# GL3227_Core.net
KiCad netlist of a schematic drawn in Altium Designer
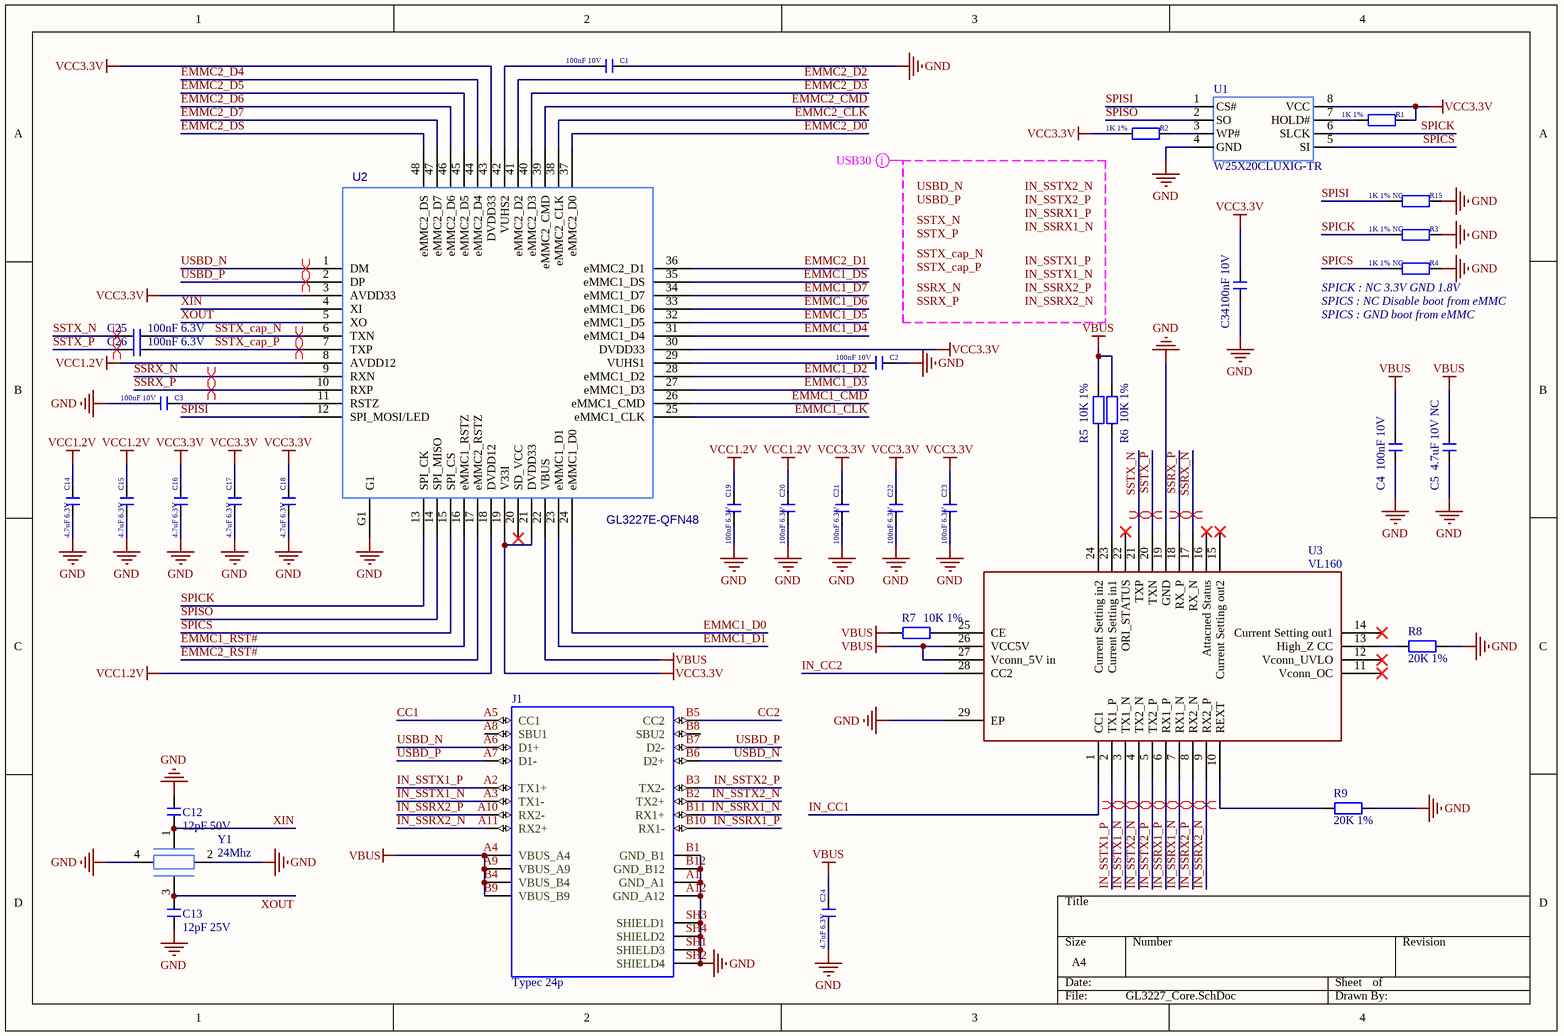
[diagram p0: GL3227_Core.SchDoc]

(export (version "E")
  (design (tool "Eeschema 10.0.6"))
  (components
    (comp (ref "C1")
      (value "100nF 10V")
      (footprint "C0402_NS")
      (description "无极性贴片电容")
      (fields (field (name "版权归属") "源创客"))
      (libsource (lib "Capacitor") (part "C"))
    )
    (comp (ref "C2")
      (value "100nF 10V")
      (footprint "C0402_NS")
      (description "无极性贴片电容")
      (fields (field (name "版权归属") "源创客"))
      (libsource (lib "Capacitor") (part "C"))
    )
    (comp (ref "C3")
      (value "100nF 10V")
      (footprint "C0402_NS")
      (description "无极性贴片电容")
      (fields (field (name "版权归属") "源创客"))
      (libsource (lib "Capacitor") (part "C"))
    )
    (comp (ref "C4")
      (value "100nF 10V")
      (footprint "C0402_NS")
      (description "无极性贴片电容")
      (fields (field (name "版权归属") "源创客"))
      (libsource (lib "Capacitor") (part "C"))
    )
    (comp (ref "C5")
      (value "4.7uF 10V NC")
      (footprint "C0402_NS")
      (description "无极性贴片电容")
      (fields (field (name "版权归属") "源创客"))
      (libsource (lib "Capacitor") (part "C"))
    )
    (comp (ref "C12")
      (value "12pF 50V")
      (footprint "C0402_NS")
      (description "无极性贴片电容")
      (fields (field (name "版权归属") "源创客"))
      (libsource (lib "Capacitor") (part "C"))
    )
    (comp (ref "C13")
      (value "12pF 25V")
      (footprint "C0402_NS")
      (description "无极性贴片电容")
      (fields (field (name "版权归属") "源创客"))
      (libsource (lib "Capacitor") (part "C"))
    )
    (comp (ref "C14")
      (value "4.7uF 6.3V")
      (footprint "C0402_NS")
      (description "无极性贴片电容")
      (fields (field (name "版权归属") "源创客"))
      (libsource (lib "Capacitor") (part "C"))
    )
    (comp (ref "C15")
      (value "4.7uF 6.3V")
      (footprint "C0402_NS")
      (description "无极性贴片电容")
      (fields (field (name "版权归属") "源创客"))
      (libsource (lib "Capacitor") (part "C"))
    )
    (comp (ref "C16")
      (value "4.7uF 6.3V")
      (footprint "C0402_NS")
      (description "无极性贴片电容")
      (fields (field (name "版权归属") "源创客"))
      (libsource (lib "Capacitor") (part "C"))
    )
    (comp (ref "C17")
      (value "4.7uF 6.3V")
      (footprint "C0402_NS")
      (description "无极性贴片电容")
      (fields (field (name "版权归属") "源创客"))
      (libsource (lib "Capacitor") (part "C"))
    )
    (comp (ref "C18")
      (value "4.7uF 6.3V")
      (footprint "C0402_NS")
      (description "无极性贴片电容")
      (fields (field (name "版权归属") "源创客"))
      (libsource (lib "Capacitor") (part "C"))
    )
    (comp (ref "C19")
      (value "100nF 6.3V")
      (footprint "C0402_NS")
      (description "无极性贴片电容")
      (fields (field (name "版权归属") "源创客"))
      (libsource (lib "Capacitor") (part "C"))
    )
    (comp (ref "C20")
      (value "100nF 6.3V")
      (footprint "C0402_NS")
      (description "无极性贴片电容")
      (fields (field (name "版权归属") "源创客"))
      (libsource (lib "Capacitor") (part "C"))
    )
    (comp (ref "C21")
      (value "100nF 6.3V")
      (footprint "C0402_NS")
      (description "无极性贴片电容")
      (fields (field (name "版权归属") "源创客"))
      (libsource (lib "Capacitor") (part "C"))
    )
    (comp (ref "C22")
      (value "100nF 6.3V")
      (footprint "C0402_NS")
      (description "无极性贴片电容")
      (fields (field (name "版权归属") "源创客"))
      (libsource (lib "Capacitor") (part "C"))
    )
    (comp (ref "C23")
      (value "100nF 6.3V")
      (footprint "C0402_NS")
      (description "无极性贴片电容")
      (fields (field (name "版权归属") "源创客"))
      (libsource (lib "Capacitor") (part "C"))
    )
    (comp (ref "C24")
      (value "4.7uF 6.3V")
      (footprint "C0402_NS")
      (description "无极性贴片电容")
      (fields (field (name "版权归属") "源创客"))
      (libsource (lib "Capacitor") (part "C"))
    )
    (comp (ref "C25")
      (value "100nF 6.3V")
      (footprint "C0402_NS")
      (description "无极性贴片电容")
      (fields (field (name "版权归属") "源创客"))
      (libsource (lib "Capacitor") (part "C"))
    )
    (comp (ref "C26")
      (value "100nF 6.3V")
      (footprint "C0402_NS")
      (description "无极性贴片电容")
      (fields (field (name "版权归属") "源创客"))
      (libsource (lib "Capacitor") (part "C"))
    )
    (comp (ref "C34")
      (value "100nF 10V")
      (footprint "C0402_NS")
      (description "无极性贴片电容")
      (fields (field (name "版权归属") "源创客"))
      (libsource (lib "Capacitor") (part "C"))
    )
    (comp (ref "J1")
      (value "Typec 24p")
      (footprint "USB-C-SMD_TYPEC-1103-BRP24")
      (fields (field (name "MF") "Molex") (field (name "MP") "1054500101"))
      (libsource (lib "Connector-USB") (part "Typec 24p"))
    )
    (comp (ref "R1")
      (value "1K 1%")
      (footprint "R0402_NS")
      (description "贴片电阻")
      (fields (field (name "版权归属") "源创客"))
      (libsource (lib "Resistor") (part "R"))
    )
    (comp (ref "R2")
      (value "1K 1%")
      (footprint "R0402_NS")
      (description "贴片电阻")
      (fields (field (name "版权归属") "源创客"))
      (libsource (lib "Resistor") (part "R"))
    )
    (comp (ref "R3")
      (value "1K 1% NC")
      (footprint "R0402_NS")
      (description "贴片电阻")
      (fields (field (name "版权归属") "源创客"))
      (libsource (lib "Resistor") (part "R"))
    )
    (comp (ref "R4")
      (value "1K 1% NC")
      (footprint "R0402_NS")
      (description "贴片电阻")
      (fields (field (name "版权归属") "源创客"))
      (libsource (lib "Resistor") (part "R"))
    )
    (comp (ref "R5")
      (value "10K 1%")
      (footprint "R0402_NS")
      (description "贴片电阻")
      (fields (field (name "版权归属") "源创客"))
      (libsource (lib "Resistor") (part "R"))
    )
    (comp (ref "R6")
      (value "10K 1%")
      (footprint "R0402_NS")
      (description "贴片电阻")
      (fields (field (name "版权归属") "源创客"))
      (libsource (lib "Resistor") (part "R"))
    )
    (comp (ref "R7")
      (value "10K 1%")
      (footprint "R0402_NS")
      (description "贴片电阻")
      (fields (field (name "版权归属") "源创客"))
      (libsource (lib "Resistor") (part "R"))
    )
    (comp (ref "R8")
      (value "20K 1%")
      (footprint "R0402_NS")
      (description "贴片电阻")
      (fields (field (name "版权归属") "源创客"))
      (libsource (lib "Resistor") (part "R"))
    )
    (comp (ref "R9")
      (value "20K 1%")
      (footprint "R0402_NS")
      (description "贴片电阻")
      (fields (field (name "版权归属") "源创客"))
      (libsource (lib "Resistor") (part "R"))
    )
    (comp (ref "R15")
      (value "1K 1% NC")
      (footprint "R0402_NS")
      (description "贴片电阻")
      (fields (field (name "版权归属") "源创客"))
      (libsource (lib "Resistor") (part "R"))
    )
    (comp (ref "U1")
      (value "W25X20CLUXIG-TR")
      (footprint "USON-8_L1.5-W1.5-P0.40-BL-EP")
      (libsource (lib "Flash") (part "P25D40H"))
    )
    (comp (ref "U2")
      (value "GL3227E-QFN48")
      (footprint "QFN48 7X7_M")
      (fields (field (name "Comment") "GL3227E-QFN48-ON2"))
      (libsource (lib "Brage") (part "GL3227E-QFN48-ON2"))
    )
    (comp (ref "U3")
      (value "VL160")
      (footprint "MQFN-28_L4.5-W3.5-P0.40-BL-EP")
      (libsource (lib "Brage") (part "VL160"))
    )
    (comp (ref "Y1") (value "24Mhz") (footprint "OSC-1612-4P") (libsource (lib "Crystal") (part "Crystal")))
  )
  (nets
    (net (code "1") (name "/CC1") (class "Default")
      (node (ref "J1") (pin "A5") (pinfunction "CC1_A5") (pintype "bidirectional"))
    )
    (net (code "2") (name "/CC2") (class "Default")
      (node (ref "J1") (pin "B5") (pinfunction "CC2_B5") (pintype "bidirectional"))
    )
    (net (code "3") (name "/EMMC1_CLK") (class "Default")
      (node (ref "U2") (pin "25") (pinfunction "eMMC1_CLK_25") (pintype "passive"))
    )
    (net (code "4") (name "/EMMC1_CMD") (class "Default")
      (node (ref "U2") (pin "26") (pinfunction "eMMC1_CMD_26") (pintype "passive"))
    )
    (net (code "5") (name "/EMMC1_D0") (class "Default")
      (node (ref "U2") (pin "24") (pinfunction "eMMC1_D0_24") (pintype "passive"))
    )
    (net (code "6") (name "/EMMC1_D1") (class "Default")
      (node (ref "U2") (pin "23") (pinfunction "eMMC1_D1_23") (pintype "passive"))
    )
    (net (code "7") (name "/EMMC1_D2") (class "Default")
      (node (ref "U2") (pin "28") (pinfunction "eMMC1_D2_28") (pintype "passive"))
    )
    (net (code "8") (name "/EMMC1_D3") (class "Default")
      (node (ref "U2") (pin "27") (pinfunction "eMMC1_D3_27") (pintype "passive"))
    )
    (net (code "9") (name "/EMMC1_D4") (class "Default")
      (node (ref "U2") (pin "31") (pinfunction "eMMC1_D4_31") (pintype "passive"))
    )
    (net (code "10") (name "/EMMC1_D5") (class "Default")
      (node (ref "U2") (pin "32") (pinfunction "eMMC1_D5_32") (pintype "passive"))
    )
    (net (code "11") (name "/EMMC1_D6") (class "Default")
      (node (ref "U2") (pin "33") (pinfunction "eMMC1_D6_33") (pintype "passive"))
    )
    (net (code "12") (name "/EMMC1_D7") (class "Default")
      (node (ref "U2") (pin "34") (pinfunction "eMMC1_D7_34") (pintype "passive"))
    )
    (net (code "13") (name "/EMMC1_DS") (class "Default")
      (node (ref "U2") (pin "35") (pinfunction "eMMC1_DS_35") (pintype "passive"))
    )
    (net (code "14") (name "/EMMC1_RST#") (class "Default")
      (node (ref "U2") (pin "16") (pinfunction "eMMC1_RSTZ_16") (pintype "passive"))
    )
    (net (code "15") (name "/EMMC2_CLK") (class "Default")
      (node (ref "U2") (pin "38") (pinfunction "eMMC2_CLK_38") (pintype "passive"))
    )
    (net (code "16") (name "/EMMC2_CMD") (class "Default")
      (node (ref "U2") (pin "39") (pinfunction "eMMC2_CMD_39") (pintype "passive"))
    )
    (net (code "17") (name "/EMMC2_D0") (class "Default")
      (node (ref "U2") (pin "37") (pinfunction "eMMC2_D0_37") (pintype "passive"))
    )
    (net (code "18") (name "/EMMC2_D1") (class "Default")
      (node (ref "U2") (pin "36") (pinfunction "eMMC2_D1_36") (pintype "passive"))
    )
    (net (code "19") (name "/EMMC2_D2") (class "Default")
      (node (ref "U2") (pin "41") (pinfunction "eMMC2_D2_41") (pintype "passive"))
    )
    (net (code "20") (name "/EMMC2_D3") (class "Default")
      (node (ref "U2") (pin "40") (pinfunction "eMMC2_D3_40") (pintype "passive"))
    )
    (net (code "21") (name "/EMMC2_D4") (class "Default")
      (node (ref "U2") (pin "44") (pinfunction "eMMC2_D4_44") (pintype "passive"))
    )
    (net (code "22") (name "/EMMC2_D5") (class "Default")
      (node (ref "U2") (pin "45") (pinfunction "eMMC2_D5_45") (pintype "passive"))
    )
    (net (code "23") (name "/EMMC2_D6") (class "Default")
      (node (ref "U2") (pin "46") (pinfunction "eMMC2_D6_46") (pintype "passive"))
    )
    (net (code "24") (name "/EMMC2_D7") (class "Default")
      (node (ref "U2") (pin "47") (pinfunction "eMMC2_D7_47") (pintype "passive"))
    )
    (net (code "25") (name "/EMMC2_DS") (class "Default")
      (node (ref "U2") (pin "48") (pinfunction "eMMC2_DS_48") (pintype "passive"))
    )
    (net (code "26") (name "/EMMC2_RST#") (class "Default")
      (node (ref "U2") (pin "17") (pinfunction "eMMC2_RSTZ_17") (pintype "passive"))
    )
    (net (code "27") (name "/IN_CC1") (class "Default")
      (node (ref "U3") (pin "1") (pinfunction "CC1_1") (pintype "passive"))
    )
    (net (code "28") (name "/IN_CC2") (class "Default")
      (node (ref "U3") (pin "28") (pinfunction "CC2_28") (pintype "passive"))
    )
    (net (code "29") (name "/IN_SSRX1_N") (class "Default")
      (node (ref "J1") (pin "B11") (pinfunction "RX1+_B11") (pintype "bidirectional"))
      (node (ref "U3") (pin "7") (pinfunction "RX1_N_7") (pintype "passive"))
    )
    (net (code "30") (name "/IN_SSRX1_P") (class "Default")
      (node (ref "J1") (pin "B10") (pinfunction "RX1-_B10") (pintype "bidirectional"))
      (node (ref "U3") (pin "6") (pinfunction "RX1_P_6") (pintype "passive"))
    )
    (net (code "31") (name "/IN_SSRX2_N") (class "Default")
      (node (ref "J1") (pin "A11") (pinfunction "RX2+_A11") (pintype "bidirectional"))
      (node (ref "U3") (pin "9") (pinfunction "RX2_P_9") (pintype "passive"))
    )
    (net (code "32") (name "/IN_SSRX2_P") (class "Default")
      (node (ref "J1") (pin "A10") (pinfunction "RX2-_A10") (pintype "bidirectional"))
      (node (ref "U3") (pin "8") (pinfunction "RX2_N_8") (pintype "passive"))
    )
    (net (code "33") (name "/IN_SSTX1_N") (class "Default")
      (node (ref "J1") (pin "A3") (pinfunction "TX1-_A3") (pintype "bidirectional"))
      (node (ref "U3") (pin "3") (pinfunction "TX1_N_3") (pintype "passive"))
    )
    (net (code "34") (name "/IN_SSTX1_P") (class "Default")
      (node (ref "J1") (pin "A2") (pinfunction "TX1+_A2") (pintype "bidirectional"))
      (node (ref "U3") (pin "2") (pinfunction "TX1_P_2") (pintype "passive"))
    )
    (net (code "35") (name "/IN_SSTX2_N") (class "Default")
      (node (ref "J1") (pin "B2") (pinfunction "TX2+_B2") (pintype "bidirectional"))
      (node (ref "U3") (pin "4") (pinfunction "TX2_N_4") (pintype "passive"))
    )
    (net (code "36") (name "/IN_SSTX2_P") (class "Default")
      (node (ref "J1") (pin "B3") (pinfunction "TX2-_B3") (pintype "bidirectional"))
      (node (ref "U3") (pin "5") (pinfunction "TX2_P_5") (pintype "passive"))
    )
    (net (code "37") (name "/SPICK") (class "Default")
      (node (ref "R3") (pin "2") (pinfunction "2_2") (pintype "passive"))
      (node (ref "U1") (pin "6") (pinfunction "SLCK_6") (pintype "passive"))
      (node (ref "U2") (pin "13") (pinfunction "SPI_CK_13") (pintype "passive"))
    )
    (net (code "38") (name "/SPICS") (class "Default")
      (node (ref "R4") (pin "2") (pinfunction "2_2") (pintype "passive"))
      (node (ref "U1") (pin "5") (pinfunction "SI_5") (pintype "passive"))
      (node (ref "U2") (pin "15") (pinfunction "SPI_CS_15") (pintype "passive"))
    )
    (net (code "39") (name "/SPISI") (class "Default")
      (node (ref "R15") (pin "2") (pinfunction "2_2") (pintype "passive"))
      (node (ref "U1") (pin "1") (pinfunction "CS#_1") (pintype "passive"))
      (node (ref "U2") (pin "12") (pinfunction "SPI_MOSI/LED_12") (pintype "passive"))
    )
    (net (code "40") (name "/SPISO") (class "Default")
      (node (ref "U1") (pin "2") (pinfunction "SO_2") (pintype "passive"))
      (node (ref "U2") (pin "14") (pinfunction "SPI_MISO_14") (pintype "passive"))
    )
    (net (code "41") (name "/SSRX_N") (class "Default")
      (node (ref "U2") (pin "9") (pinfunction "RXN_9") (pintype "passive"))
      (node (ref "U3") (pin "17") (pinfunction "RX_N_17") (pintype "passive"))
    )
    (net (code "42") (name "/SSRX_P") (class "Default")
      (node (ref "U2") (pin "10") (pinfunction "RXP_10") (pintype "passive"))
      (node (ref "U3") (pin "18") (pinfunction "RX_P_18") (pintype "passive"))
    )
    (net (code "43") (name "/SSTX_N") (class "Default")
      (node (ref "C25") (pin "2") (pinfunction "2_2") (pintype "passive"))
      (node (ref "U3") (pin "21") (pinfunction "TXP_21") (pintype "passive"))
    )
    (net (code "44") (name "/SSTX_P") (class "Default")
      (node (ref "C26") (pin "2") (pinfunction "2_2") (pintype "passive"))
      (node (ref "U3") (pin "20") (pinfunction "TXN_20") (pintype "passive"))
    )
    (net (code "45") (name "/SSTX_cap_N") (class "Default")
      (node (ref "C25") (pin "1") (pinfunction "1_1") (pintype "passive"))
      (node (ref "U2") (pin "6") (pinfunction "TXN_6") (pintype "passive"))
    )
    (net (code "46") (name "/SSTX_cap_P") (class "Default")
      (node (ref "C26") (pin "1") (pinfunction "1_1") (pintype "passive"))
      (node (ref "U2") (pin "7") (pinfunction "TXP_7") (pintype "passive"))
    )
    (net (code "47") (name "/USBD_N") (class "Default")
      (node (ref "J1") (pin "A6") (pinfunction "D1+_A6") (pintype "bidirectional"))
      (node (ref "J1") (pin "B6") (pinfunction "D2+_B6") (pintype "bidirectional"))
      (node (ref "U2") (pin "1") (pinfunction "DM_1") (pintype "passive"))
    )
    (net (code "48") (name "/USBD_P") (class "Default")
      (node (ref "J1") (pin "A7") (pinfunction "D1-_A7") (pintype "bidirectional"))
      (node (ref "J1") (pin "B7") (pinfunction "D2-_B7") (pintype "bidirectional"))
      (node (ref "U2") (pin "2") (pinfunction "DP_2") (pintype "passive"))
    )
    (net (code "49") (name "/XIN") (class "Default")
      (node (ref "C12") (pin "2") (pinfunction "2_2") (pintype "passive"))
      (node (ref "U2") (pin "4") (pinfunction "XI_4") (pintype "passive"))
      (node (ref "Y1") (pin "1") (pinfunction "XTAL_N_1") (pintype "passive"))
    )
    (net (code "50") (name "/XOUT") (class "Default")
      (node (ref "C13") (pin "2") (pinfunction "2_2") (pintype "passive"))
      (node (ref "U2") (pin "5") (pinfunction "XO_5") (pintype "passive"))
      (node (ref "Y1") (pin "3") (pinfunction "XTAL_P_3") (pintype "passive"))
    )
    (net (code "51") (name "GND") (class "Default")
      (node (ref "C1") (pin "1") (pinfunction "1_1") (pintype "passive"))
      (node (ref "C12") (pin "1") (pinfunction "1_1") (pintype "passive"))
      (node (ref "C13") (pin "1") (pinfunction "1_1") (pintype "passive"))
      (node (ref "C14") (pin "2") (pinfunction "2_2") (pintype "passive"))
      (node (ref "C15") (pin "2") (pinfunction "2_2") (pintype "passive"))
      (node (ref "C16") (pin "2") (pinfunction "2_2") (pintype "passive"))
      (node (ref "C17") (pin "2") (pinfunction "2_2") (pintype "passive"))
      (node (ref "C18") (pin "2") (pinfunction "2_2") (pintype "passive"))
      (node (ref "C19") (pin "2") (pinfunction "2_2") (pintype "passive"))
      (node (ref "C2") (pin "1") (pinfunction "1_1") (pintype "passive"))
      (node (ref "C20") (pin "2") (pinfunction "2_2") (pintype "passive"))
      (node (ref "C21") (pin "2") (pinfunction "2_2") (pintype "passive"))
      (node (ref "C22") (pin "2") (pinfunction "2_2") (pintype "passive"))
      (node (ref "C23") (pin "2") (pinfunction "2_2") (pintype "passive"))
      (node (ref "C24") (pin "2") (pinfunction "2_2") (pintype "passive"))
      (node (ref "C3") (pin "2") (pinfunction "2_2") (pintype "passive"))
      (node (ref "C34") (pin "1") (pinfunction "1_1") (pintype "passive"))
      (node (ref "C4") (pin "1") (pinfunction "1_1") (pintype "passive"))
      (node (ref "C5") (pin "1") (pinfunction "1_1") (pintype "passive"))
      (node (ref "J1") (pin "A1") (pinfunction "GND_A1_A1") (pintype "power_in"))
      (node (ref "J1") (pin "A12") (pinfunction "GND_A12_A12") (pintype "power_in"))
      (node (ref "J1") (pin "B1") (pinfunction "GND_B1_B1") (pintype "power_in"))
      (node (ref "J1") (pin "B12") (pinfunction "GND_B12_B12") (pintype "power_in"))
      (node (ref "J1") (pin "SH1") (pinfunction "SHIELD3_SH1") (pintype "passive"))
      (node (ref "J1") (pin "SH2") (pinfunction "SHIELD4_SH2") (pintype "passive"))
      (node (ref "J1") (pin "SH3") (pinfunction "SHIELD1_SH3") (pintype "passive"))
      (node (ref "J1") (pin "SH4") (pinfunction "SHIELD2_SH4") (pintype "passive"))
      (node (ref "R15") (pin "1") (pinfunction "1_1") (pintype "passive"))
      (node (ref "R3") (pin "1") (pinfunction "1_1") (pintype "passive"))
      (node (ref "R4") (pin "1") (pinfunction "1_1") (pintype "passive"))
      (node (ref "R8") (pin "1") (pinfunction "1_1") (pintype "passive"))
      (node (ref "R9") (pin "1") (pinfunction "1_1") (pintype "passive"))
      (node (ref "U1") (pin "4") (pinfunction "GND_4") (pintype "passive"))
      (node (ref "U2") (pin "G1") (pinfunction "G1_G1") (pintype "passive"))
      (node (ref "U3") (pin "19") (pinfunction "GND_19") (pintype "passive"))
      (node (ref "U3") (pin "29") (pinfunction "EP_29") (pintype "passive"))
      (node (ref "Y1") (pin "2") (pinfunction "GND_2") (pintype "passive"))
      (node (ref "Y1") (pin "4") (pinfunction "GND_4") (pintype "passive"))
    )
    (net (code "52") (name "Net-(U1-HOLD#)") (class "Default")
      (node (ref "R1") (pin "2") (pinfunction "2_2") (pintype "passive"))
      (node (ref "U1") (pin "7") (pinfunction "HOLD#_7") (pintype "passive"))
    )
    (net (code "53") (name "Net-(U1-WP#)") (class "Default")
      (node (ref "R2") (pin "1") (pinfunction "1_1") (pintype "passive"))
      (node (ref "U1") (pin "3") (pinfunction "WP#_3") (pintype "passive"))
    )
    (net (code "54") (name "Net-(U2-RSTZ)") (class "Default")
      (node (ref "C3") (pin "1") (pinfunction "1_1") (pintype "passive"))
      (node (ref "U2") (pin "11") (pinfunction "RSTZ_11") (pintype "passive"))
    )
    (net (code "55") (name "Net-(U2-VUHS1)") (class "Default")
      (node (ref "C2") (pin "2") (pinfunction "2_2") (pintype "passive"))
      (node (ref "U2") (pin "29") (pinfunction "VUHS1_29") (pintype "power_in"))
    )
    (net (code "56") (name "Net-(U2-VUHS2)") (class "Default")
      (node (ref "C1") (pin "2") (pinfunction "2_2") (pintype "passive"))
      (node (ref "U2") (pin "42") (pinfunction "VUHS2_42") (pintype "power_in"))
    )
    (net (code "57") (name "Net-(U3-CE)") (class "Default")
      (node (ref "R7") (pin "1") (pinfunction "1_1") (pintype "passive"))
      (node (ref "U3") (pin "25") (pinfunction "CE_25") (pintype "passive"))
    )
    (net (code "58") (name "Net-(U3-Current_Setting_in1)") (class "Default")
      (node (ref "R6") (pin "2") (pinfunction "2_2") (pintype "passive"))
      (node (ref "U3") (pin "23") (pinfunction "Current_Setting_in1_23") (pintype "passive"))
    )
    (net (code "59") (name "Net-(U3-Current_Setting_in2)") (class "Default")
      (node (ref "R5") (pin "2") (pinfunction "2_2") (pintype "passive"))
      (node (ref "U3") (pin "24") (pinfunction "Current_Setting_in2_24") (pintype "passive"))
    )
    (net (code "60") (name "Net-(U3-High_Z_CC)") (class "Default")
      (node (ref "R8") (pin "2") (pinfunction "2_2") (pintype "passive"))
      (node (ref "U3") (pin "13") (pinfunction "High_Z_CC_13") (pintype "passive"))
    )
    (net (code "61") (name "Net-(U3-REXT)") (class "Default")
      (node (ref "R9") (pin "2") (pinfunction "2_2") (pintype "passive"))
      (node (ref "U3") (pin "10") (pinfunction "REXT_10") (pintype "passive"))
    )
    (net (code "62") (name "VBUS") (class "Default")
      (node (ref "C24") (pin "1") (pinfunction "1_1") (pintype "passive"))
      (node (ref "C4") (pin "2") (pinfunction "2_2") (pintype "passive"))
      (node (ref "C5") (pin "2") (pinfunction "2_2") (pintype "passive"))
      (node (ref "J1") (pin "A4") (pinfunction "VBUS_A4_A4") (pintype "power_in"))
      (node (ref "J1") (pin "A9") (pinfunction "VBUS_A9_A9") (pintype "power_in"))
      (node (ref "J1") (pin "B4") (pinfunction "VBUS_B4_B4") (pintype "power_in"))
      (node (ref "J1") (pin "B9") (pinfunction "VBUS_B9_B9") (pintype "power_in"))
      (node (ref "R5") (pin "1") (pinfunction "1_1") (pintype "passive"))
      (node (ref "R6") (pin "1") (pinfunction "1_1") (pintype "passive"))
      (node (ref "R7") (pin "2") (pinfunction "2_2") (pintype "passive"))
      (node (ref "U2") (pin "22") (pinfunction "VBUS_22") (pintype "power_in"))
      (node (ref "U3") (pin "26") (pinfunction "VCC5V_26") (pintype "passive"))
      (node (ref "U3") (pin "27") (pinfunction "Vconn_5V_in_27") (pintype "passive"))
    )
    (net (code "63") (name "VCC1.2V") (class "Default")
      (node (ref "C14") (pin "1") (pinfunction "1_1") (pintype "passive"))
      (node (ref "C15") (pin "1") (pinfunction "1_1") (pintype "passive"))
      (node (ref "C19") (pin "1") (pinfunction "1_1") (pintype "passive"))
      (node (ref "C20") (pin "1") (pinfunction "1_1") (pintype "passive"))
      (node (ref "U2") (pin "18") (pinfunction "DVDD12_18") (pintype "power_in"))
      (node (ref "U2") (pin "8") (pinfunction "AVDD12_8") (pintype "power_in"))
    )
    (net (code "64") (name "VCC3.3V") (class "Default")
      (node (ref "C16") (pin "1") (pinfunction "1_1") (pintype "passive"))
      (node (ref "C17") (pin "1") (pinfunction "1_1") (pintype "passive"))
      (node (ref "C18") (pin "1") (pinfunction "1_1") (pintype "passive"))
      (node (ref "C21") (pin "1") (pinfunction "1_1") (pintype "passive"))
      (node (ref "C22") (pin "1") (pinfunction "1_1") (pintype "passive"))
      (node (ref "C23") (pin "1") (pinfunction "1_1") (pintype "passive"))
      (node (ref "C34") (pin "2") (pinfunction "2_2") (pintype "passive"))
      (node (ref "R1") (pin "1") (pinfunction "1_1") (pintype "passive"))
      (node (ref "R2") (pin "2") (pinfunction "2_2") (pintype "passive"))
      (node (ref "U1") (pin "8") (pinfunction "VCC_8") (pintype "passive"))
      (node (ref "U2") (pin "19") (pinfunction "V33I_19") (pintype "power_in"))
      (node (ref "U2") (pin "21") (pinfunction "DVDD33_21") (pintype "power_in"))
      (node (ref "U2") (pin "3") (pinfunction "AVDD33_3") (pintype "power_in"))
      (node (ref "U2") (pin "30") (pinfunction "DVDD33_30") (pintype "power_in"))
      (node (ref "U2") (pin "43") (pinfunction "DVDD33_43") (pintype "power_in"))
    )
    (net (code "65") (name "unconnected-(J1-SBU1-PadA8)") (class "Default")
      (node (ref "J1") (pin "A8") (pinfunction "SBU1_A8") (pintype "bidirectional"))
    )
    (net (code "66") (name "unconnected-(J1-SBU2-PadB8)") (class "Default")
      (node (ref "J1") (pin "B8") (pinfunction "SBU2_B8") (pintype "bidirectional"))
    )
    (net (code "67") (name "unconnected-(U2-SD_VCC-Pad20)") (class "Default")
      (node (ref "U2") (pin "20") (pinfunction "SD_VCC_20") (pintype "passive+no_connect"))
    )
    (net (code "68") (name "unconnected-(U3-Attacned_Status-Pad16)") (class "Default")
      (node (ref "U3") (pin "16") (pinfunction "Attacned_Status_16") (pintype "passive+no_connect"))
    )
    (net (code "69") (name "unconnected-(U3-Current_Setting_out1-Pad14)") (class "Default")
      (node (ref "U3") (pin "14") (pinfunction "Current_Setting_out1_14") (pintype "passive+no_connect"))
    )
    (net (code "70") (name "unconnected-(U3-Current_Setting_out2-Pad15)") (class "Default")
      (node (ref "U3") (pin "15") (pinfunction "Current_Setting_out2_15") (pintype "passive+no_connect"))
    )
    (net (code "71") (name "unconnected-(U3-ORI_STATUS-Pad22)") (class "Default")
      (node (ref "U3") (pin "22") (pinfunction "ORI_STATUS_22") (pintype "passive+no_connect"))
    )
    (net (code "72") (name "unconnected-(U3-Vconn_OC-Pad11)") (class "Default")
      (node (ref "U3") (pin "11") (pinfunction "Vconn_OC_11") (pintype "passive+no_connect"))
    )
    (net (code "73") (name "unconnected-(U3-Vconn_UVLO-Pad12)") (class "Default")
      (node (ref "U3") (pin "12") (pinfunction "Vconn_UVLO_12") (pintype "passive+no_connect"))
    )
  )
)
